# Gadget-Box-PiZero.net
KiCad netlist of a schematic drawn in EAGLE
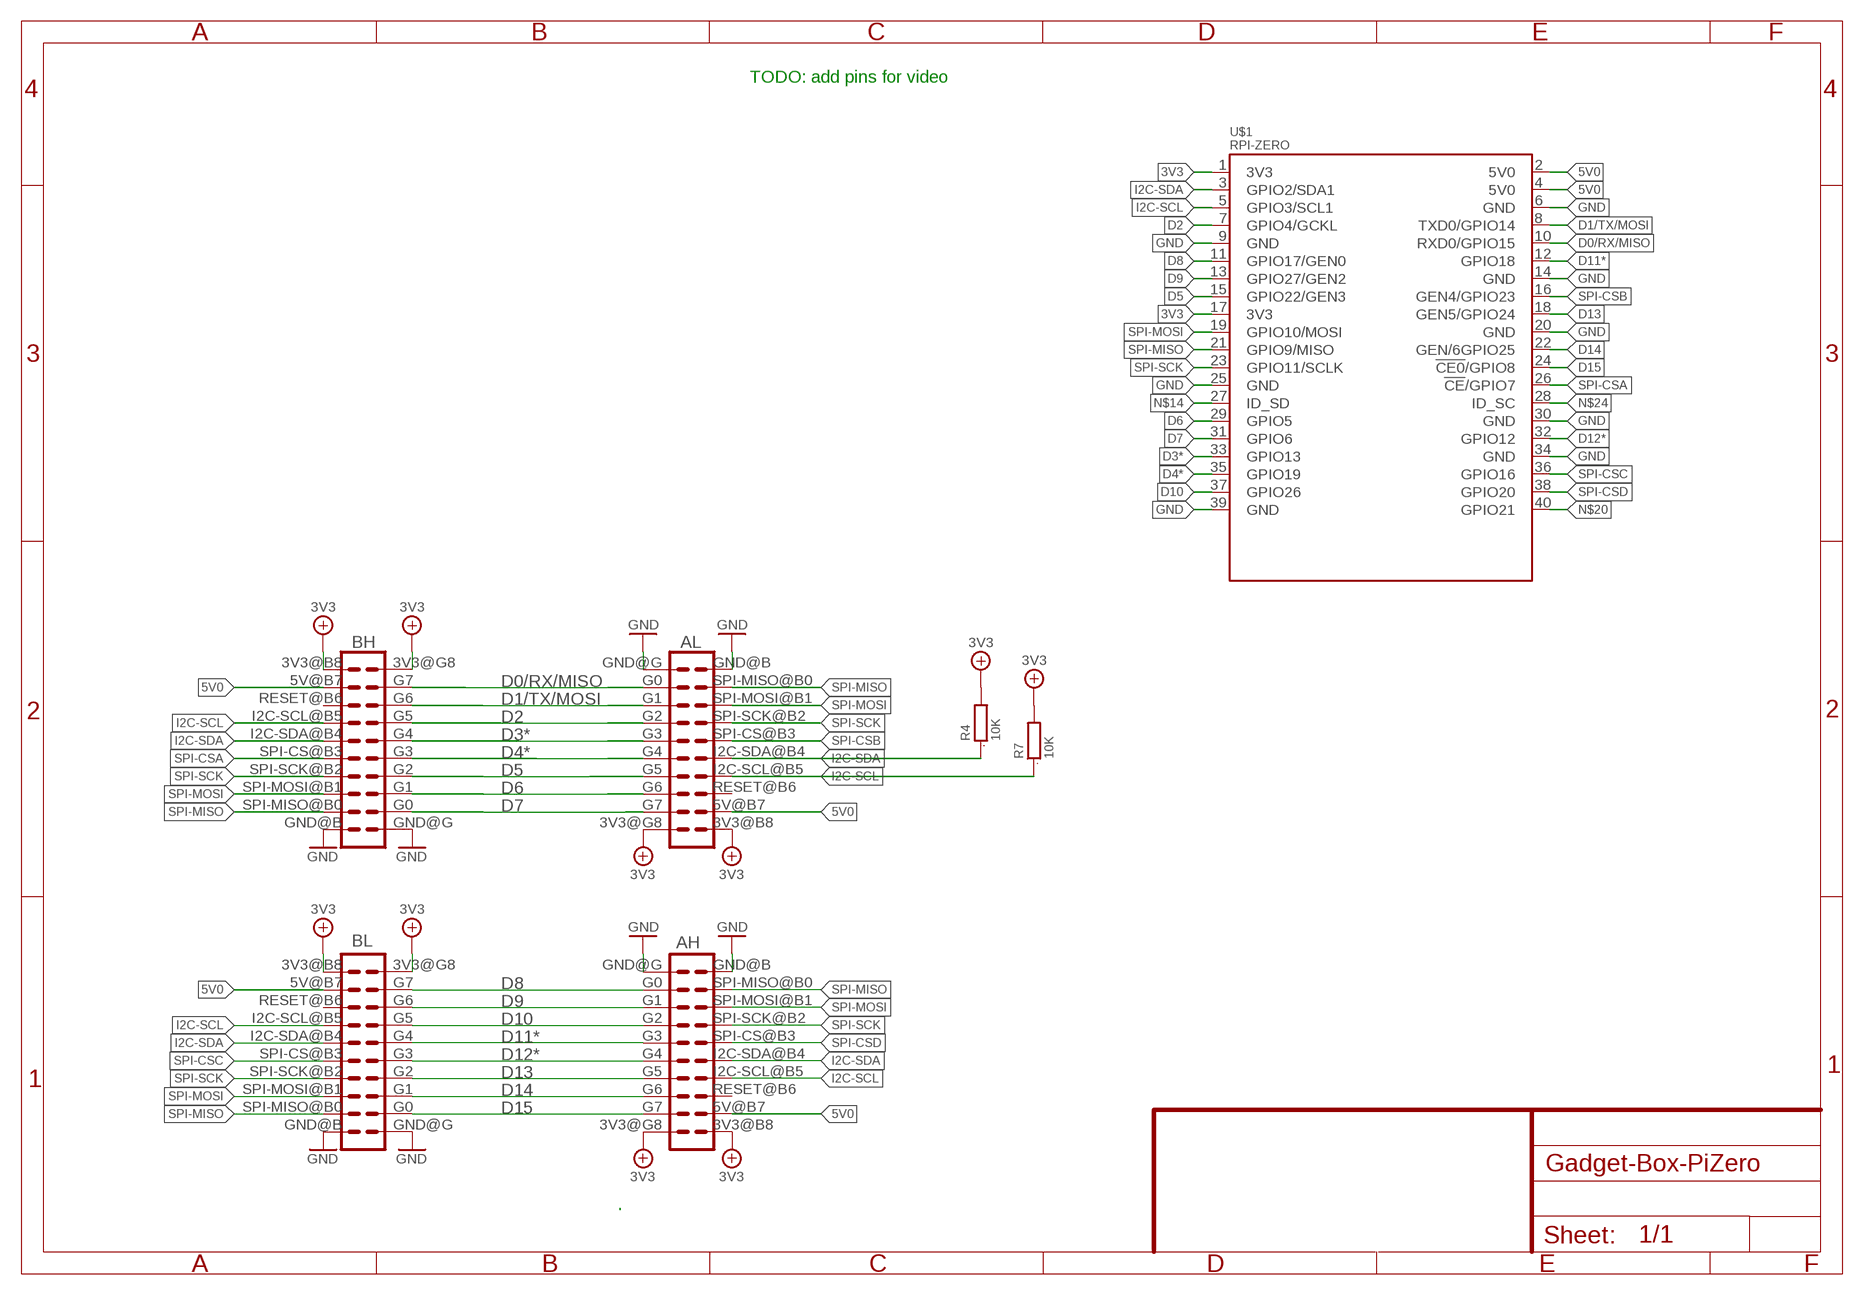
[diagram p0: schematic, sheet 1]

(export (version "E")
  (design (tool "Eeschema 10.0.6"))
  (components
    (comp (ref "AH")
      (value "ECOGECOG_SLOT_ALT1")
      (footprint "eagle-import:ECOG_ALT1")
      (libsource (lib "eagle-import") (part "ECOGECOG_SLOT_ALT1"))
    )
    (comp (ref "AL")
      (value "ECOGECOG_SLOT_ALT1")
      (footprint "eagle-import:ECOG_ALT1")
      (libsource (lib "eagle-import") (part "ECOGECOG_SLOT_ALT1"))
    )
    (comp (ref "BH")
      (value "ECOGECOG_SLOT_ALT1")
      (footprint "eagle-import:ECOG_ALT1")
      (libsource (lib "eagle-import") (part "ECOGECOG_SLOT_ALT1"))
    )
    (comp (ref "BL")
      (value "ECOGECOG_SLOT_ALT1")
      (footprint "eagle-import:ECOG_ALT1")
      (libsource (lib "eagle-import") (part "ECOGECOG_SLOT_ALT1"))
    )
    (comp (ref "R4")
      (value "10K")
      (footprint "eagle-import:0603")
      (fields
        (field (name "PARTNO") "RC0603JR-0710KL,YAGEO (VA),dk,311-10KGRCT-ND,RES SMD 10K OHM 5% 1/10W 0603 , REF36")
      )
      (libsource (lib "eagle-import") (part "R0603"))
    )
    (comp (ref "R7")
      (value "10K")
      (footprint "eagle-import:0603")
      (fields
        (field (name "PARTNO") "RC0603JR-0710KL,YAGEO (VA),dk,311-10KGRCT-ND,RES SMD 10K OHM 5% 1/10W 0603 , REF36")
      )
      (libsource (lib "eagle-import") (part "R0603"))
    )
    (comp (ref "U$1")
      (value "RPI-ZERO")
      (footprint "eagle-import:RASPBERRYPI_BASTELSTUBE_V13_RASPI_BOARD_B+_FULL")
      (libsource (lib "eagle-import") (part "RPI-ZERO"))
    )
  )
  (nets
    (net (code "1") (name "3V3") (class "Default")
      (node (ref "AH") (pin "3V3@B8") (pinfunction "3V3_3V3@B8") (pintype "passive"))
      (node (ref "AH") (pin "3V3@G8") (pinfunction "3V3_3V3@G8") (pintype "passive"))
      (node (ref "AL") (pin "3V3@B8") (pinfunction "3V3_3V3@B8") (pintype "passive"))
      (node (ref "AL") (pin "3V3@G8") (pinfunction "3V3_3V3@G8") (pintype "passive"))
      (node (ref "BH") (pin "3V3@B8") (pinfunction "3V3_3V3@B8") (pintype "passive"))
      (node (ref "BH") (pin "3V3@G8") (pinfunction "3V3_3V3@G8") (pintype "passive"))
      (node (ref "BL") (pin "3V3@B8") (pinfunction "3V3_3V3@B8") (pintype "passive"))
      (node (ref "BL") (pin "3V3@G8") (pinfunction "3V3_3V3@G8") (pintype "passive"))
      (node (ref "R4") (pin "2") (pinfunction "2_2") (pintype "passive"))
      (node (ref "R7") (pin "2") (pinfunction "2_2") (pintype "passive"))
      (node (ref "U$1") (pin "1") (pinfunction "3V3_1") (pintype "power_in"))
      (node (ref "U$1") (pin "17") (pinfunction "3V3_17") (pintype "power_in"))
    )
    (net (code "2") (name "5V0") (class "Default")
      (node (ref "AH") (pin "5V@B7") (pinfunction "5V_5V@B7") (pintype "passive"))
      (node (ref "AL") (pin "5V@B7") (pinfunction "5V_5V@B7") (pintype "passive"))
      (node (ref "BH") (pin "5V@B7") (pinfunction "5V_5V@B7") (pintype "passive"))
      (node (ref "BL") (pin "5V@B7") (pinfunction "5V_5V@B7") (pintype "passive"))
      (node (ref "U$1") (pin "2") (pinfunction "5V0_2") (pintype "power_in"))
      (node (ref "U$1") (pin "4") (pinfunction "5V0_4") (pintype "power_in"))
    )
    (net (code "3") (name "D0{slash}RX{slash}MISO") (class "Default")
      (node (ref "AL") (pin "G0") (pinfunction "G0_G0") (pintype "passive"))
      (node (ref "BH") (pin "G7") (pinfunction "G7_G7") (pintype "passive"))
      (node (ref "U$1") (pin "10") (pinfunction "RXD0/GPIO15_10") (pintype "bidirectional"))
    )
    (net (code "4") (name "D1{slash}TX{slash}MOSI") (class "Default")
      (node (ref "AL") (pin "G1") (pinfunction "G1_G1") (pintype "passive"))
      (node (ref "BH") (pin "G6") (pinfunction "G6_G6") (pintype "passive"))
      (node (ref "U$1") (pin "8") (pinfunction "TXD0/GPIO14_8") (pintype "bidirectional"))
    )
    (net (code "5") (name "D2") (class "Default")
      (node (ref "AL") (pin "G2") (pinfunction "G2_G2") (pintype "passive"))
      (node (ref "BH") (pin "G5") (pinfunction "G5_G5") (pintype "passive"))
      (node (ref "U$1") (pin "7") (pinfunction "GPIO4/GCKL_7") (pintype "bidirectional"))
    )
    (net (code "6") (name "D3*") (class "Default")
      (node (ref "AL") (pin "G3") (pinfunction "G3_G3") (pintype "passive"))
      (node (ref "BH") (pin "G4") (pinfunction "G4_G4") (pintype "passive"))
      (node (ref "U$1") (pin "33") (pinfunction "GPIO13_33") (pintype "bidirectional"))
    )
    (net (code "7") (name "D4*") (class "Default")
      (node (ref "AL") (pin "G4") (pinfunction "G4_G4") (pintype "passive"))
      (node (ref "BH") (pin "G3") (pinfunction "G3_G3") (pintype "passive"))
      (node (ref "U$1") (pin "35") (pinfunction "GPIO19_35") (pintype "bidirectional"))
    )
    (net (code "8") (name "D5") (class "Default")
      (node (ref "AL") (pin "G5") (pinfunction "G5_G5") (pintype "passive"))
      (node (ref "BH") (pin "G2") (pinfunction "G2_G2") (pintype "passive"))
      (node (ref "U$1") (pin "15") (pinfunction "GPIO22/GEN3_15") (pintype "bidirectional"))
    )
    (net (code "9") (name "D6") (class "Default")
      (node (ref "AL") (pin "G6") (pinfunction "G6_G6") (pintype "passive"))
      (node (ref "BH") (pin "G1") (pinfunction "G1_G1") (pintype "passive"))
      (node (ref "U$1") (pin "29") (pinfunction "GPIO5_29") (pintype "bidirectional"))
    )
    (net (code "10") (name "D7") (class "Default")
      (node (ref "AL") (pin "G7") (pinfunction "G7_G7") (pintype "passive"))
      (node (ref "BH") (pin "G0") (pinfunction "G0_G0") (pintype "passive"))
      (node (ref "U$1") (pin "31") (pinfunction "GPIO6_31") (pintype "bidirectional"))
    )
    (net (code "11") (name "D8") (class "Default")
      (node (ref "AH") (pin "G0") (pinfunction "G0_G0") (pintype "passive"))
      (node (ref "BL") (pin "G7") (pinfunction "G7_G7") (pintype "passive"))
      (node (ref "U$1") (pin "11") (pinfunction "GPIO17/GEN0_11") (pintype "bidirectional"))
    )
    (net (code "12") (name "D9") (class "Default")
      (node (ref "AH") (pin "G1") (pinfunction "G1_G1") (pintype "passive"))
      (node (ref "BL") (pin "G6") (pinfunction "G6_G6") (pintype "passive"))
      (node (ref "U$1") (pin "13") (pinfunction "GPIO27/GEN2_13") (pintype "bidirectional"))
    )
    (net (code "13") (name "D10") (class "Default")
      (node (ref "AH") (pin "G2") (pinfunction "G2_G2") (pintype "passive"))
      (node (ref "BL") (pin "G5") (pinfunction "G5_G5") (pintype "passive"))
      (node (ref "U$1") (pin "37") (pinfunction "GPIO26_37") (pintype "bidirectional"))
    )
    (net (code "14") (name "D11*") (class "Default")
      (node (ref "AH") (pin "G3") (pinfunction "G3_G3") (pintype "passive"))
      (node (ref "BL") (pin "G4") (pinfunction "G4_G4") (pintype "passive"))
      (node (ref "U$1") (pin "12") (pinfunction "GPIO18_12") (pintype "bidirectional"))
    )
    (net (code "15") (name "D12*") (class "Default")
      (node (ref "AH") (pin "G4") (pinfunction "G4_G4") (pintype "passive"))
      (node (ref "BL") (pin "G3") (pinfunction "G3_G3") (pintype "passive"))
      (node (ref "U$1") (pin "32") (pinfunction "GPIO12_32") (pintype "bidirectional"))
    )
    (net (code "16") (name "D13") (class "Default")
      (node (ref "AH") (pin "G5") (pinfunction "G5_G5") (pintype "passive"))
      (node (ref "BL") (pin "G2") (pinfunction "G2_G2") (pintype "passive"))
      (node (ref "U$1") (pin "18") (pinfunction "GEN5/GPIO24_18") (pintype "bidirectional"))
    )
    (net (code "17") (name "D14") (class "Default")
      (node (ref "AH") (pin "G6") (pinfunction "G6_G6") (pintype "passive"))
      (node (ref "BL") (pin "G1") (pinfunction "G1_G1") (pintype "passive"))
      (node (ref "U$1") (pin "22") (pinfunction "GEN/6GPIO25_22") (pintype "bidirectional"))
    )
    (net (code "18") (name "D15") (class "Default")
      (node (ref "AH") (pin "G7") (pinfunction "G7_G7") (pintype "passive"))
      (node (ref "BL") (pin "G0") (pinfunction "G0_G0") (pintype "passive"))
      (node (ref "U$1") (pin "24") (pinfunction "~{CE0}/GPIO8_24") (pintype "bidirectional"))
    )
    (net (code "19") (name "GND") (class "Default")
      (node (ref "AH") (pin "GND@B") (pinfunction "GND_GND@B") (pintype "passive"))
      (node (ref "AH") (pin "GND@G") (pinfunction "GND_GND@G") (pintype "passive"))
      (node (ref "AL") (pin "GND@B") (pinfunction "GND_GND@B") (pintype "passive"))
      (node (ref "AL") (pin "GND@G") (pinfunction "GND_GND@G") (pintype "passive"))
      (node (ref "BH") (pin "GND@B") (pinfunction "GND_GND@B") (pintype "passive"))
      (node (ref "BH") (pin "GND@G") (pinfunction "GND_GND@G") (pintype "passive"))
      (node (ref "BL") (pin "GND@B") (pinfunction "GND_GND@B") (pintype "passive"))
      (node (ref "BL") (pin "GND@G") (pinfunction "GND_GND@G") (pintype "passive"))
      (node (ref "U$1") (pin "14") (pinfunction "GND_14") (pintype "power_in"))
      (node (ref "U$1") (pin "20") (pinfunction "GND_20") (pintype "power_in"))
      (node (ref "U$1") (pin "25") (pinfunction "GND_25") (pintype "power_in"))
      (node (ref "U$1") (pin "30") (pinfunction "GND_30") (pintype "power_in"))
      (node (ref "U$1") (pin "34") (pinfunction "GND_34") (pintype "power_in"))
      (node (ref "U$1") (pin "39") (pinfunction "GND_39") (pintype "power_in"))
      (node (ref "U$1") (pin "6") (pinfunction "GND_6") (pintype "power_in"))
      (node (ref "U$1") (pin "9") (pinfunction "GND_9") (pintype "power_in"))
    )
    (net (code "20") (name "I2C-SCL") (class "Default")
      (node (ref "AH") (pin "I2C-SCL@B5") (pinfunction "I2C-SCL_I2C-SCL@B5") (pintype "passive"))
      (node (ref "AL") (pin "I2C-SCL@B5") (pinfunction "I2C-SCL_I2C-SCL@B5") (pintype "passive"))
      (node (ref "BH") (pin "I2C-SCL@B5") (pinfunction "I2C-SCL_I2C-SCL@B5") (pintype "passive"))
      (node (ref "BL") (pin "I2C-SCL@B5") (pinfunction "I2C-SCL_I2C-SCL@B5") (pintype "passive"))
      (node (ref "R7") (pin "1") (pinfunction "1_1") (pintype "passive"))
      (node (ref "U$1") (pin "5") (pinfunction "GPIO3/SCL1_5") (pintype "bidirectional"))
    )
    (net (code "21") (name "I2C-SDA") (class "Default")
      (node (ref "AH") (pin "I2C-SDA@B4") (pinfunction "I2C-SDA_I2C-SDA@B4") (pintype "passive"))
      (node (ref "AL") (pin "I2C-SDA@B4") (pinfunction "I2C-SDA_I2C-SDA@B4") (pintype "passive"))
      (node (ref "BH") (pin "I2C-SDA@B4") (pinfunction "I2C-SDA_I2C-SDA@B4") (pintype "passive"))
      (node (ref "BL") (pin "I2C-SDA@B4") (pinfunction "I2C-SDA_I2C-SDA@B4") (pintype "passive"))
      (node (ref "R4") (pin "1") (pinfunction "1_1") (pintype "passive"))
      (node (ref "U$1") (pin "3") (pinfunction "GPIO2/SDA1_3") (pintype "bidirectional"))
    )
    (net (code "22") (name "N$14") (class "Default")
      (node (ref "U$1") (pin "27") (pinfunction "ID_SD_27") (pintype "bidirectional"))
    )
    (net (code "23") (name "N$20") (class "Default")
      (node (ref "U$1") (pin "40") (pinfunction "GPIO21_40") (pintype "bidirectional"))
    )
    (net (code "24") (name "N$24") (class "Default")
      (node (ref "U$1") (pin "28") (pinfunction "ID_SC_28") (pintype "bidirectional"))
    )
    (net (code "25") (name "SPI-CSA") (class "Default")
      (node (ref "BH") (pin "SPI-CS@B3") (pinfunction "SPI-CS_SPI-CS@B3") (pintype "passive"))
      (node (ref "U$1") (pin "26") (pinfunction "~{CE}/GPIO7_26") (pintype "bidirectional"))
    )
    (net (code "26") (name "SPI-CSB") (class "Default")
      (node (ref "AL") (pin "SPI-CS@B3") (pinfunction "SPI-CS_SPI-CS@B3") (pintype "passive"))
      (node (ref "U$1") (pin "16") (pinfunction "GEN4/GPIO23_16") (pintype "bidirectional"))
    )
    (net (code "27") (name "SPI-CSC") (class "Default")
      (node (ref "BL") (pin "SPI-CS@B3") (pinfunction "SPI-CS_SPI-CS@B3") (pintype "passive"))
      (node (ref "U$1") (pin "36") (pinfunction "GPIO16_36") (pintype "bidirectional"))
    )
    (net (code "28") (name "SPI-CSD") (class "Default")
      (node (ref "AH") (pin "SPI-CS@B3") (pinfunction "SPI-CS_SPI-CS@B3") (pintype "passive"))
      (node (ref "U$1") (pin "38") (pinfunction "GPIO20_38") (pintype "bidirectional"))
    )
    (net (code "29") (name "SPI-MISO") (class "Default")
      (node (ref "AH") (pin "SPI-MISO@B0") (pinfunction "SPI-MISO_SPI-MISO@B0") (pintype "passive"))
      (node (ref "AL") (pin "SPI-MISO@B0") (pinfunction "SPI-MISO_SPI-MISO@B0") (pintype "passive"))
      (node (ref "BH") (pin "SPI-MISO@B0") (pinfunction "SPI-MISO_SPI-MISO@B0") (pintype "passive"))
      (node (ref "BL") (pin "SPI-MISO@B0") (pinfunction "SPI-MISO_SPI-MISO@B0") (pintype "passive"))
      (node (ref "U$1") (pin "21") (pinfunction "GPIO9/MISO_21") (pintype "bidirectional"))
    )
    (net (code "30") (name "SPI-MOSI") (class "Default")
      (node (ref "AH") (pin "SPI-MOSI@B1") (pinfunction "SPI-MOSI_SPI-MOSI@B1") (pintype "passive"))
      (node (ref "AL") (pin "SPI-MOSI@B1") (pinfunction "SPI-MOSI_SPI-MOSI@B1") (pintype "passive"))
      (node (ref "BH") (pin "SPI-MOSI@B1") (pinfunction "SPI-MOSI_SPI-MOSI@B1") (pintype "passive"))
      (node (ref "BL") (pin "SPI-MOSI@B1") (pinfunction "SPI-MOSI_SPI-MOSI@B1") (pintype "passive"))
      (node (ref "U$1") (pin "19") (pinfunction "GPIO10/MOSI_19") (pintype "bidirectional"))
    )
    (net (code "31") (name "SPI-SCK") (class "Default")
      (node (ref "AH") (pin "SPI-SCK@B2") (pinfunction "SPI-SCK_SPI-SCK@B2") (pintype "passive"))
      (node (ref "AL") (pin "SPI-SCK@B2") (pinfunction "SPI-SCK_SPI-SCK@B2") (pintype "passive"))
      (node (ref "BH") (pin "SPI-SCK@B2") (pinfunction "SPI-SCK_SPI-SCK@B2") (pintype "passive"))
      (node (ref "BL") (pin "SPI-SCK@B2") (pinfunction "SPI-SCK_SPI-SCK@B2") (pintype "passive"))
      (node (ref "U$1") (pin "23") (pinfunction "GPIO11/SCLK_23") (pintype "bidirectional"))
    )
    (net (code "32") (name "unconnected-(AH-RESET-PadRESET@B6)") (class "Default")
      (node (ref "AH") (pin "RESET@B6") (pinfunction "RESET_RESET@B6") (pintype "passive"))
    )
    (net (code "33") (name "unconnected-(AL-RESET-PadRESET@B6)") (class "Default")
      (node (ref "AL") (pin "RESET@B6") (pinfunction "RESET_RESET@B6") (pintype "passive"))
    )
    (net (code "34") (name "unconnected-(BH-RESET-PadRESET@B6)") (class "Default")
      (node (ref "BH") (pin "RESET@B6") (pinfunction "RESET_RESET@B6") (pintype "passive"))
    )
    (net (code "35") (name "unconnected-(BL-RESET-PadRESET@B6)") (class "Default")
      (node (ref "BL") (pin "RESET@B6") (pinfunction "RESET_RESET@B6") (pintype "passive"))
    )
  )
)
